# ORelay.net
KiCad netlist of a schematic drawn in Altium Designer
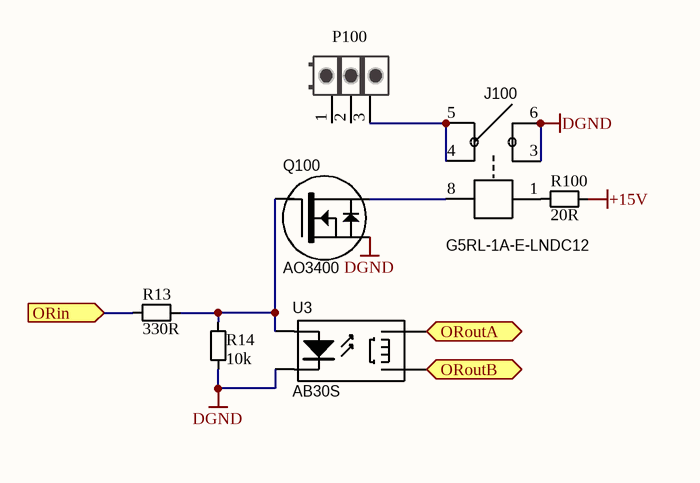
[diagram p0: ORelay.SchDoc]

(export (version "E")
  (design (tool "Eeschema 10.0.6"))
  (components
    (comp (ref "J100")
      (value "G5RL-1A-E-LNDC12")
      (footprint "GreenBox:G5RL-1A-E")
      (description "Power/Signal Relay G5RL-1A-E-LNDC12 16A 250VAC 12VDC")
      (fields (field (name "MANUFACTURER") "OMRON") (field (name "PUBLISHER") "GreenBox"))
      (libsource (lib "Relay") (part "JNDZG5RL1122"))
    )
    (comp (ref "P100")
      (value "KF7.62-3P")
      (footprint "GreenBox:KF762-3")
      (description "Header KF7.62-3P 7.62mm")
      (fields (field (name "PUBLISHER") "GreenBox"))
      (libsource (lib "Connectors") (part "PKDK03Z76200"))
    )
    (comp (ref "Q100")
      (value "AO3400")
      (footprint "GreenBox:SOT-23_N")
      (description "N-Channel MOSFET AO3400 30V 5.8A")
      (fields (field (name "MANUFACTURER") "ALPHA&OMEGA") (field (name "PUBLISHER") "GreenBox"))
      (libsource (lib "MOSFET") (part "QN42AO34000A"))
    )
    (comp (ref "R13")
      (value "330R")
      (footprint "GreenBox:0603-R")
      (description "SMD Resistor 330R 1% 1/10W 0603 100PPM")
      (fields (field (name "Comment") "Res") (field (name "PUBLISHER") "GreenBox"))
      (libsource (lib "Resistor") (part "R11C330RFBF0"))
    )
    (comp (ref "R14")
      (value "10k")
      (footprint "GreenBox:0603-R")
      (description "SMD Resistor 10k 1% 1/10W 0603 100PPM")
      (fields (field (name "Comment") "Res") (field (name "PUBLISHER") "GreenBox"))
      (libsource (lib "Resistor") (part "R11C010KFBF0"))
    )
    (comp (ref "R100")
      (value "20R")
      (footprint "GreenBox:1206-R")
      (description "SMD Resistor 20R 1% 1/4W 1206 100PPM")
      (fields (field (name "Comment") "Res") (field (name "PUBLISHER") "GreenBox"))
      (libsource (lib "Resistor") (part "R11E020RFDF0"))
    )
    (comp (ref "U3")
      (value "AB30S")
      (footprint "GreenBox:TOWARD-SOP-4")
      (description "Solid State Optronics Relay AB30S 100mA 400V 24Ω")
      (fields (field (name "MANUFACTURER") "TOWARD") (field (name "PUBLISHER") "GreenBox"))
      (libsource (lib "Optocoupler") (part "UPSCAB30S00W"))
    )
  )
  (nets
    (net (code "1") (name "+15V") (class "Default")
      (node (ref "R100") (pin "2") (pinfunction "2_2") (pintype "passive"))
    )
    (net (code "2") (name "/ORin") (class "Default")
      (node (ref "R13") (pin "1") (pinfunction "1_1") (pintype "passive"))
    )
    (net (code "3") (name "/ORoutA") (class "Default")
      (node (ref "U3") (pin "4") (pinfunction "C_4") (pintype "passive"))
    )
    (net (code "4") (name "/ORoutB") (class "Default")
      (node (ref "U3") (pin "3") (pinfunction "E_3") (pintype "passive"))
    )
    (net (code "5") (name "DGND") (class "Default")
      (node (ref "J100") (pin "3") (pinfunction "3_3") (pintype "passive"))
      (node (ref "J100") (pin "6") (pinfunction "6_6") (pintype "passive"))
      (node (ref "Q100") (pin "2") (pinfunction "S_2") (pintype "passive"))
      (node (ref "R14") (pin "2") (pinfunction "2_2") (pintype "passive"))
      (node (ref "U3") (pin "2") (pinfunction "K_2") (pintype "passive"))
    )
    (net (code "6") (name "Net-(J100-Pad1)") (class "Default")
      (node (ref "J100") (pin "1") (pinfunction "1_1") (pintype "passive"))
      (node (ref "R100") (pin "1") (pinfunction "1_1") (pintype "passive"))
    )
    (net (code "7") (name "Net-(J100-Pad4)") (class "Default")
      (node (ref "J100") (pin "4") (pinfunction "4_4") (pintype "passive"))
      (node (ref "J100") (pin "5") (pinfunction "5_5") (pintype "passive"))
      (node (ref "P100") (pin "3") (pinfunction "3_3") (pintype "passive"))
    )
    (net (code "8") (name "Net-(Q100-D)") (class "Default")
      (node (ref "J100") (pin "8") (pinfunction "8_8") (pintype "passive"))
      (node (ref "Q100") (pin "3") (pinfunction "D_3") (pintype "passive"))
    )
    (net (code "9") (name "Net-(Q100-G)") (class "Default")
      (node (ref "Q100") (pin "1") (pinfunction "G_1") (pintype "passive"))
      (node (ref "R13") (pin "2") (pinfunction "2_2") (pintype "passive"))
      (node (ref "R14") (pin "1") (pinfunction "1_1") (pintype "passive"))
      (node (ref "U3") (pin "1") (pinfunction "A_1") (pintype "passive"))
    )
    (net (code "10") (name "unconnected-(P100-Pad1)") (class "Default")
      (node (ref "P100") (pin "1") (pinfunction "1_1") (pintype "passive"))
    )
    (net (code "11") (name "unconnected-(P100-Pad2)") (class "Default")
      (node (ref "P100") (pin "2") (pinfunction "2_2") (pintype "passive"))
    )
  )
)
